# Power.net
KiCad netlist of a schematic drawn in Altium Designer
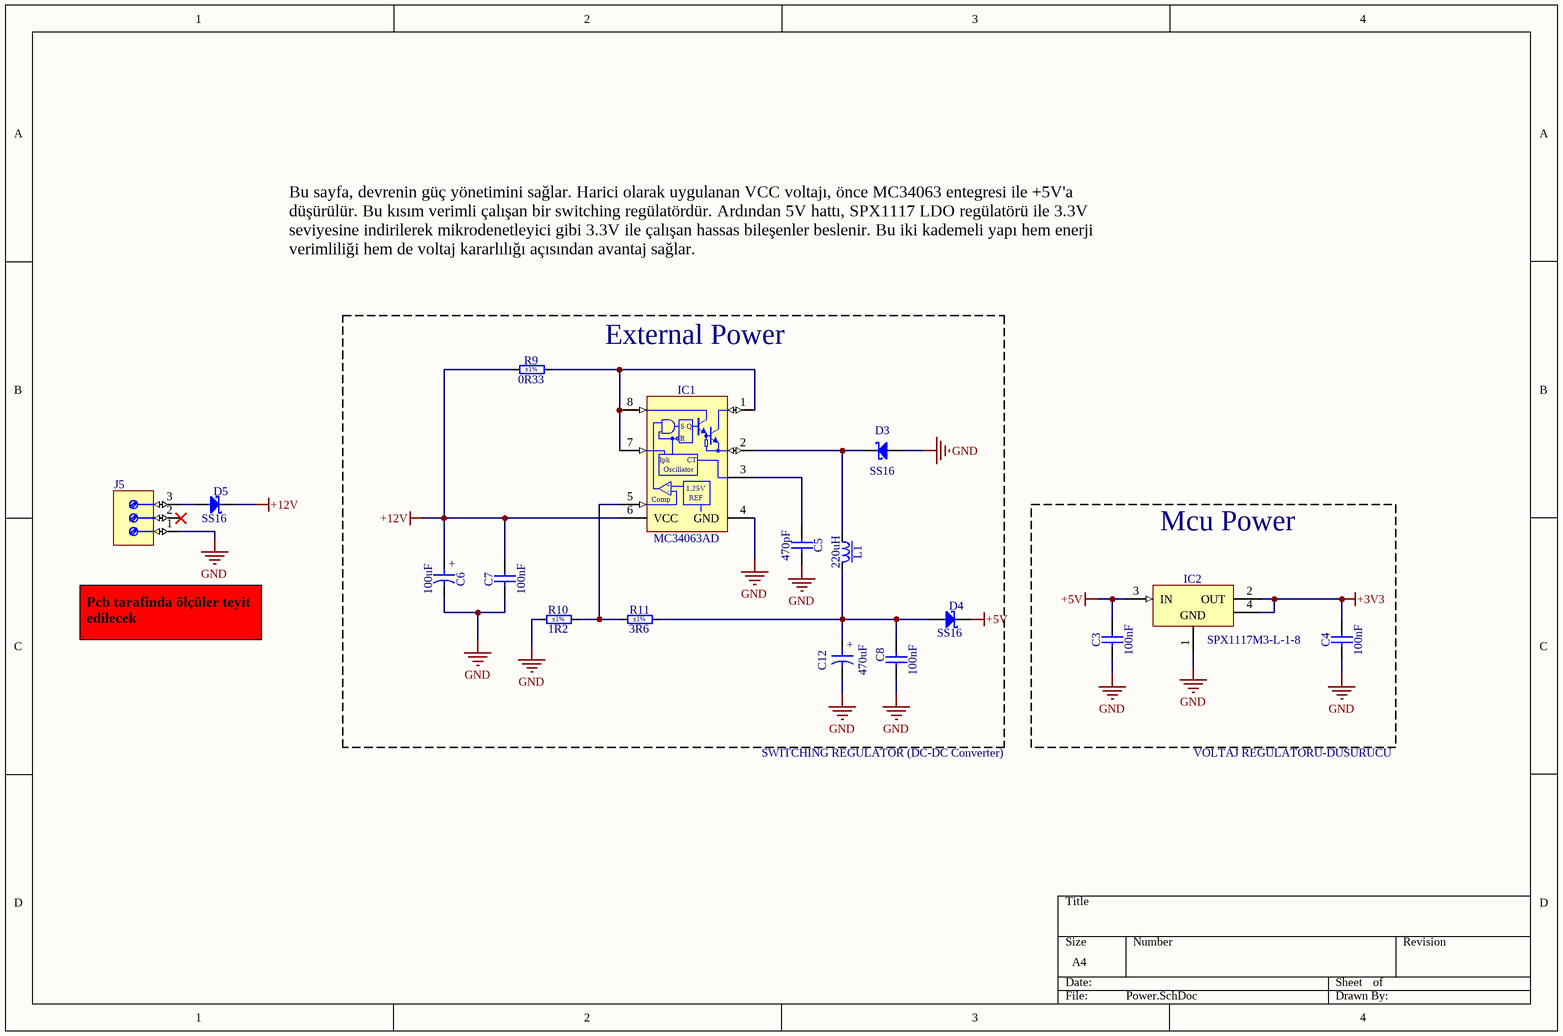
[diagram p0: Power.SchDoc]

(export (version "E")
  (design (tool "Eeschema 10.0.6"))
  (components
    (comp (ref "C3")
      (value "100nF")
      (footprint "CAPC1608X87N")
      (description "Non-polarised capacitor")
      (fields
        (field (name "PART NUMBER") "CC0603_100NF_50V_10%_X5R")
        (field (name "VOLTAGE") "50V")
        (field (name "AUTHOR") "CERN DEM MR")
      )
      (libsource (lib "Capacitors") (part "Capacitor - non polarized"))
    )
    (comp (ref "C4")
      (value "100nF")
      (footprint "CAPC1608X87N")
      (description "Non-polarised capacitor")
      (fields
        (field (name "PART NUMBER") "CC0603_100NF_50V_10%_X5R")
        (field (name "VOLTAGE") "50V")
        (field (name "AUTHOR") "CERN DEM MR")
      )
      (libsource (lib "Capacitors") (part "Capacitor - non polarized"))
    )
    (comp (ref "C5")
      (value "470pF")
      (footprint "CAPC1608X87N")
      (description "Non-polarised capacitor")
      (fields
        (field (name "PART NUMBER") "CC0603_470PF_50V_5%_NP0")
        (field (name "VOLTAGE") "50V")
        (field (name "AUTHOR") "CERN DEM JLC")
      )
      (libsource (lib "Capacitors") (part "Capacitor - non polarized"))
    )
    (comp (ref "C6")
      (value "100uF")
      (footprint "CAPMP7343X430N")
      (description "Polarised capacitor")
      (fields
        (field (name "PART NUMBER") "CTE7343-43_100UF_20V_10%_LESR0150")
        (field (name "VOLTAGE") "20V")
        (field (name "AUTHOR") "CERN DEM JLC")
      )
      (libsource (lib "Capacitors") (part "Capacitor - polarized"))
    )
    (comp (ref "C7")
      (value "100nF")
      (footprint "CAPC1608X87N")
      (description "Non-polarised capacitor")
      (fields
        (field (name "PART NUMBER") "CC0603_100NF_50V_10%_X5R")
        (field (name "VOLTAGE") "50V")
        (field (name "AUTHOR") "CERN DEM MR")
      )
      (libsource (lib "Capacitors") (part "Capacitor - non polarized"))
    )
    (comp (ref "C8")
      (value "100nF")
      (footprint "CAPC1608X87N")
      (description "Non-polarised capacitor")
      (fields
        (field (name "PART NUMBER") "CC0603_100NF_50V_10%_X5R")
        (field (name "VOLTAGE") "50V")
        (field (name "AUTHOR") "CERN DEM MR")
      )
      (libsource (lib "Capacitors") (part "Capacitor - non polarized"))
    )
    (comp (ref "C12")
      (value "470uF")
      (footprint "CAPMP7343X310N")
      (description "Polarised capacitor")
      (fields
        (field (name "PART NUMBER") "CTE7343-31_470UF_6.3V_10%")
        (field (name "VOLTAGE") "6.3V")
        (field (name "AUTHOR") "CERN DEM JLC")
      )
      (libsource (lib "Capacitors") (part "Capacitor - polarized"))
    )
    (comp (ref "D3")
      (value "SS16")
      (footprint "DIOM5127X229N")
      (description "Schottky Diode")
      (fields
        (field (name "VOLTAGE") "60V")
        (field (name "POWER") "1A")
        (field (name "AUTHOR") "CERN DEM JLC")
      )
      (libsource (lib "ICs And Semiconductors") (part "Diode Schottky"))
    )
    (comp (ref "D4")
      (value "SS16")
      (footprint "DIOM5127X229N")
      (description "Schottky Diode")
      (fields
        (field (name "VOLTAGE") "60V")
        (field (name "POWER") "1A")
        (field (name "AUTHOR") "CERN DEM JLC")
      )
      (libsource (lib "ICs And Semiconductors") (part "Diode Schottky"))
    )
    (comp (ref "D5")
      (value "SS16")
      (footprint "DIOM5127X229N")
      (description "Schottky Diode")
      (fields
        (field (name "VOLTAGE") "60V")
        (field (name "POWER") "1A")
        (field (name "AUTHOR") "CERN DEM JLC")
      )
      (libsource (lib "ICs And Semiconductors") (part "Diode Schottky"))
    )
    (comp (ref "IC1")
      (value "MC34063AD")
      (footprint "SOIC127P600X175-8N")
      (description "3V to 40V 1.5A Peak Boost/Buck/Inverting Switching Regulator")
      (fields (field (name "MANUFACTURER") "TEXAS INSTRUMENTS") (field (name "AUTHOR") "CERN DEM JLC"))
      (libsource (lib "ICs And Semiconductors") (part "MC34063A"))
    )
    (comp (ref "IC2")
      (value "SPX1117M3-L-1-8")
      (footprint "SOT230P700X180-4N")
      (description "3-Terminal Regulator 1=GND 2=OUT 3=IN 4=OUT")
      (fields (field (name "MANUFACTURER") "EXAR") (field (name "AUTHOR") "CERN DEM JLC"))
      (libsource (lib "ICs And Semiconductors") (part "REG3+1 1GND-2OUT-3IN+4OUT"))
    )
    (comp (ref "J5")
      (value "~")
      (footprint "PHOENIX_1715734")
      (description "Terminal Block, 3 Positions, Screw Connection")
      (fields
        (field (name "PART NUMBER") "PHOENIX_1715734")
        (field (name "MANUFACTURER") "PHOENIX CONTACT")
        (field (name "AUTHOR") "CERN DEM JLC")
      )
      (libsource (lib "Connectors") (part "Terminal Block_3 Positions_Screw Connection"))
    )
    (comp (ref "L1")
      (value "220uH")
      (footprint "IND_EPCOS_B82464-G4")
      (description "Inductor With Core")
      (fields
        (field (name "PART NUMBER") "IND_470UH_20%_EPCOS_B82464-G4")
        (field (name "POWER") "0.5A")
        (field (name "AUTHOR") "CERN DEM JLC")
      )
      (libsource (lib "Inductors & Transformers") (part "Inductor With Magnetic core"))
    )
    (comp (ref "R9")
      (value "0R33")
      (footprint "RESC3216X65N")
      (description "Resistor - 1%")
      (fields
        (field (name "TOLERANCE") "±1%")
        (field (name "PART NUMBER") "R1206_0R33_1%_0.5W_600PPM")
        (field (name "POWER") "0.5W")
        (field (name "AUTHOR") "CERN DEM JMW")
      )
      (libsource (lib "Resistors") (part "Resistor - 1%"))
    )
    (comp (ref "R10")
      (value "1R2")
      (footprint "RESC1608X55N")
      (description "Resistor - 1%")
      (fields
        (field (name "TOLERANCE") "±1%")
        (field (name "PART NUMBER") "R0603_1R2_1%_0.1W_200PPM")
        (field (name "POWER") "0.1W")
        (field (name "AUTHOR") "CERN DEM JLC")
      )
      (libsource (lib "Resistors") (part "Resistor - 1%"))
    )
    (comp (ref "R11")
      (value "3R6")
      (footprint "RESC1608X55N")
      (description "Resistor - 1%")
      (fields
        (field (name "TOLERANCE") "±1%")
        (field (name "PART NUMBER") "R0603_3R6_1%_0.1W_200PPM")
        (field (name "POWER") "0.1W")
        (field (name "AUTHOR") "CERN DEM JLC")
      )
      (libsource (lib "Resistors") (part "Resistor - 1%"))
    )
  )
  (nets
    (net (code "1") (name "+3V3") (class "Default")
      (node (ref "C4") (pin "2") (pinfunction "2_2") (pintype "passive"))
      (node (ref "IC2") (pin "2") (pinfunction "OUT_2") (pintype "power_in"))
      (node (ref "IC2") (pin "4") (pinfunction "OUT_4") (pintype "power_in"))
    )
    (net (code "2") (name "+5V") (class "Default")
      (node (ref "C3") (pin "2") (pinfunction "2_2") (pintype "passive"))
      (node (ref "D4") (pin "1") (pinfunction "C_1") (pintype "passive"))
      (node (ref "IC2") (pin "3") (pinfunction "IN_3") (pintype "input"))
    )
    (net (code "3") (name "+12V") (class "Default")
      (node (ref "C6") (pin "1") (pinfunction "1_1") (pintype "passive"))
      (node (ref "C7") (pin "2") (pinfunction "2_2") (pintype "passive"))
      (node (ref "D5") (pin "1") (pinfunction "C_1") (pintype "passive"))
      (node (ref "IC1") (pin "6") (pinfunction "VCC_6") (pintype "power_in"))
      (node (ref "R9") (pin "1") (pinfunction "1_1") (pintype "passive"))
    )
    (net (code "4") (name "GND") (class "Default")
      (node (ref "C12") (pin "2") (pinfunction "2_2") (pintype "passive"))
      (node (ref "C3") (pin "1") (pinfunction "1_1") (pintype "passive"))
      (node (ref "C4") (pin "1") (pinfunction "1_1") (pintype "passive"))
      (node (ref "C5") (pin "2") (pinfunction "2_2") (pintype "passive"))
      (node (ref "C6") (pin "2") (pinfunction "2_2") (pintype "passive"))
      (node (ref "C7") (pin "1") (pinfunction "1_1") (pintype "passive"))
      (node (ref "C8") (pin "1") (pinfunction "1_1") (pintype "passive"))
      (node (ref "D3") (pin "2") (pinfunction "A_2") (pintype "passive"))
      (node (ref "IC1") (pin "4") (pinfunction "GND_4") (pintype "power_in"))
      (node (ref "IC2") (pin "1") (pinfunction "GND_1") (pintype "power_in"))
      (node (ref "J5") (pin "1") (pinfunction "1_1") (pintype "bidirectional"))
      (node (ref "R10") (pin "1") (pinfunction "1_1") (pintype "passive"))
    )
    (net (code "5") (name "Net-(D3-C)") (class "Default")
      (node (ref "D3") (pin "1") (pinfunction "C_1") (pintype "passive"))
      (node (ref "IC1") (pin "2") (pinfunction "SWE_2") (pintype "bidirectional"))
      (node (ref "L1") (pin "1") (pinfunction "1_1") (pintype "passive"))
    )
    (net (code "6") (name "Net-(D4-A)") (class "Default")
      (node (ref "C12") (pin "1") (pinfunction "1_1") (pintype "passive"))
      (node (ref "C8") (pin "2") (pinfunction "2_2") (pintype "passive"))
      (node (ref "D4") (pin "2") (pinfunction "A_2") (pintype "passive"))
      (node (ref "L1") (pin "2") (pinfunction "2_2") (pintype "passive"))
      (node (ref "R11") (pin "2") (pinfunction "2_2") (pintype "passive"))
    )
    (net (code "7") (name "Net-(D5-A)") (class "Default")
      (node (ref "D5") (pin "2") (pinfunction "A_2") (pintype "passive"))
      (node (ref "J5") (pin "3") (pinfunction "3_3") (pintype "bidirectional"))
    )
    (net (code "8") (name "Net-(IC1-COMP)") (class "Default")
      (node (ref "IC1") (pin "5") (pinfunction "COMP_5") (pintype "input"))
      (node (ref "R10") (pin "2") (pinfunction "2_2") (pintype "passive"))
      (node (ref "R11") (pin "1") (pinfunction "1_1") (pintype "passive"))
    )
    (net (code "9") (name "Net-(IC1-DRVC)") (class "Default")
      (node (ref "IC1") (pin "1") (pinfunction "SWC_1") (pintype "bidirectional"))
      (node (ref "IC1") (pin "7") (pinfunction "Ipk_7") (pintype "input"))
      (node (ref "IC1") (pin "8") (pinfunction "DRVC_8") (pintype "input"))
      (node (ref "R9") (pin "2") (pinfunction "2_2") (pintype "passive"))
    )
    (net (code "10") (name "Net-(IC1-TC)") (class "Default")
      (node (ref "C5") (pin "1") (pinfunction "1_1") (pintype "passive"))
      (node (ref "IC1") (pin "3") (pinfunction "TC_3") (pintype "passive"))
    )
    (net (code "11") (name "unconnected-(J5-Pad2)") (class "Default")
      (node (ref "J5") (pin "2") (pinfunction "2_2") (pintype "bidirectional+no_connect"))
    )
  )
)
